# TwoFoot_SchDoc.net
KiCad netlist of a schematic drawn in Altium Designer
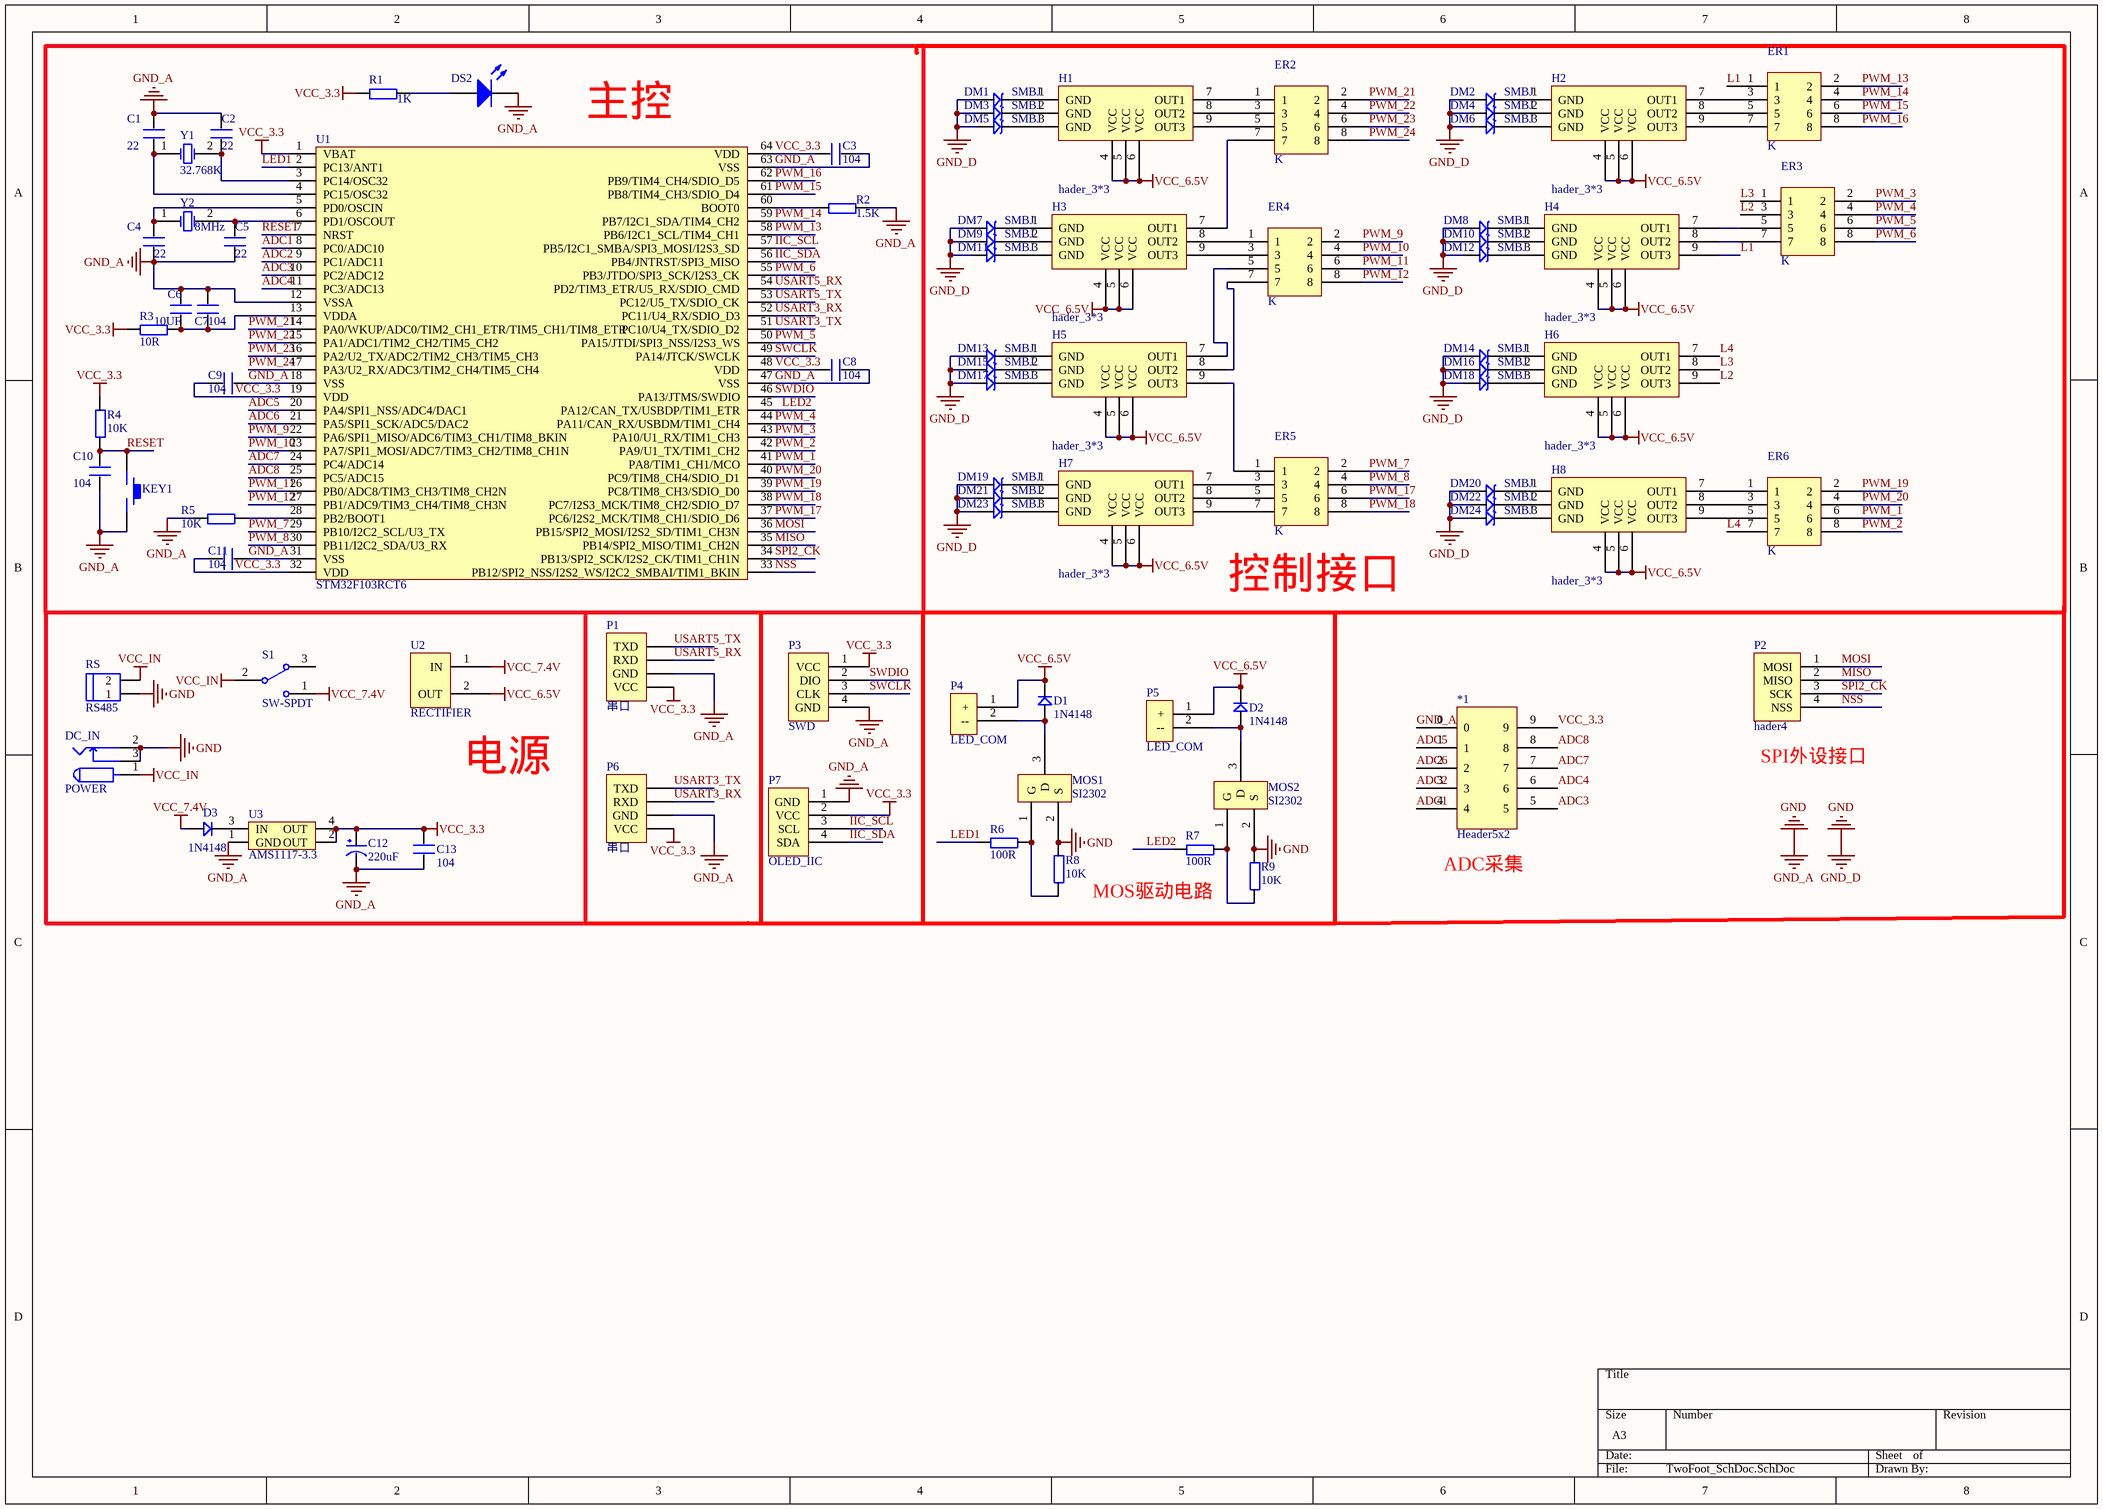
[diagram p0: TwoFoot_SchDoc.SchDoc]

(export (version "E")
  (design (tool "Eeschema 10.0.6"))
  (components
    (comp (ref "*1") (value "Header5x2") (footprint "HDR2X5") (libsource (lib "Schlib1") (part "Header5x2")))
    (comp (ref "C1") (value "22") (footprint "0603P") (libsource (lib "Schlib1") (part "C")))
    (comp (ref "C2") (value "22") (footprint "0603P") (libsource (lib "Schlib1") (part "C")))
    (comp (ref "C3") (value "104") (footprint "0603P") (libsource (lib "Schlib1") (part "C")))
    (comp (ref "C4") (value "22") (footprint "0603P") (libsource (lib "Schlib1") (part "C")))
    (comp (ref "C5") (value "22") (footprint "0603P") (libsource (lib "Schlib1") (part "C")))
    (comp (ref "C6") (value "10UF") (footprint "0603P") (libsource (lib "Schlib1") (part "C")))
    (comp (ref "C7") (value "104") (footprint "0603P") (libsource (lib "Schlib1") (part "C")))
    (comp (ref "C8") (value "104") (footprint "0603P") (libsource (lib "Schlib1") (part "C")))
    (comp (ref "C9") (value "104") (footprint "0603P") (libsource (lib "Schlib1") (part "C")))
    (comp (ref "C10") (value "104") (footprint "0603P") (libsource (lib "Schlib1") (part "C")))
    (comp (ref "C11") (value "104") (footprint "0603P") (libsource (lib "Schlib1") (part "C")))
    (comp (ref "C12") (value "220uF") (footprint "Cap1000uF") (libsource (lib "Schlib1") (part "CAP")))
    (comp (ref "C13") (value "104") (footprint "0603P") (libsource (lib "Schlib1") (part "C")))
    (comp (ref "D1") (value "1N4148") (footprint "DIODE_SOP") (libsource (lib "Schlib1") (part "D")))
    (comp (ref "D2") (value "1N4148") (footprint "DIODE_SOP") (libsource (lib "Schlib1") (part "D")))
    (comp (ref "D3") (value "1N4148") (footprint "DIODE_SOP") (libsource (lib "Schlib1") (part "D")))
    (comp (ref "DC_IN")
      (value "POWER")
      (footprint "POWER_INDC")
      (libsource (lib "Schlib1") (part "POWER_INDC"))
    )
    (comp (ref "DM1")
      (value "SMBJ")
      (footprint "SMBJ")
      (description "保险管5.0A")
      (libsource (lib "Schlib1") (part "SMBJ"))
    )
    (comp (ref "DM2")
      (value "SMBJ")
      (footprint "SMBJ")
      (description "保险管5.0A")
      (libsource (lib "Schlib1") (part "SMBJ"))
    )
    (comp (ref "DM3")
      (value "SMBJ")
      (footprint "SMBJ")
      (description "保险管5.0A")
      (libsource (lib "Schlib1") (part "SMBJ"))
    )
    (comp (ref "DM4")
      (value "SMBJ")
      (footprint "SMBJ")
      (description "保险管5.0A")
      (libsource (lib "Schlib1") (part "SMBJ"))
    )
    (comp (ref "DM5")
      (value "SMBJ")
      (footprint "SMBJ")
      (description "保险管5.0A")
      (libsource (lib "Schlib1") (part "SMBJ"))
    )
    (comp (ref "DM6")
      (value "SMBJ")
      (footprint "SMBJ")
      (description "保险管5.0A")
      (libsource (lib "Schlib1") (part "SMBJ"))
    )
    (comp (ref "DM7")
      (value "SMBJ")
      (footprint "SMBJ")
      (description "保险管5.0A")
      (libsource (lib "Schlib1") (part "SMBJ"))
    )
    (comp (ref "DM8")
      (value "SMBJ")
      (footprint "SMBJ")
      (description "保险管5.0A")
      (libsource (lib "Schlib1") (part "SMBJ"))
    )
    (comp (ref "DM9")
      (value "SMBJ")
      (footprint "SMBJ")
      (description "保险管5.0A")
      (libsource (lib "Schlib1") (part "SMBJ"))
    )
    (comp (ref "DM10")
      (value "SMBJ")
      (footprint "SMBJ")
      (description "保险管5.0A")
      (libsource (lib "Schlib1") (part "SMBJ"))
    )
    (comp (ref "DM11")
      (value "SMBJ")
      (footprint "SMBJ")
      (description "保险管5.0A")
      (libsource (lib "Schlib1") (part "SMBJ"))
    )
    (comp (ref "DM12")
      (value "SMBJ")
      (footprint "SMBJ")
      (description "保险管5.0A")
      (libsource (lib "Schlib1") (part "SMBJ"))
    )
    (comp (ref "DM13")
      (value "SMBJ")
      (footprint "SMBJ")
      (description "保险管5.0A")
      (libsource (lib "Schlib1") (part "SMBJ"))
    )
    (comp (ref "DM14")
      (value "SMBJ")
      (footprint "SMBJ")
      (description "保险管5.0A")
      (libsource (lib "Schlib1") (part "SMBJ"))
    )
    (comp (ref "DM15")
      (value "SMBJ")
      (footprint "SMBJ")
      (description "保险管5.0A")
      (libsource (lib "Schlib1") (part "SMBJ"))
    )
    (comp (ref "DM16")
      (value "SMBJ")
      (footprint "SMBJ")
      (description "保险管5.0A")
      (libsource (lib "Schlib1") (part "SMBJ"))
    )
    (comp (ref "DM17")
      (value "SMBJ")
      (footprint "SMBJ")
      (description "保险管5.0A")
      (libsource (lib "Schlib1") (part "SMBJ"))
    )
    (comp (ref "DM18")
      (value "SMBJ")
      (footprint "SMBJ")
      (description "保险管5.0A")
      (libsource (lib "Schlib1") (part "SMBJ"))
    )
    (comp (ref "DM19")
      (value "SMBJ")
      (footprint "SMBJ")
      (description "保险管5.0A")
      (libsource (lib "Schlib1") (part "SMBJ"))
    )
    (comp (ref "DM20")
      (value "SMBJ")
      (footprint "SMBJ")
      (description "保险管5.0A")
      (libsource (lib "Schlib1") (part "SMBJ"))
    )
    (comp (ref "DM21")
      (value "SMBJ")
      (footprint "SMBJ")
      (description "保险管5.0A")
      (libsource (lib "Schlib1") (part "SMBJ"))
    )
    (comp (ref "DM22")
      (value "SMBJ")
      (footprint "SMBJ")
      (description "保险管5.0A")
      (libsource (lib "Schlib1") (part "SMBJ"))
    )
    (comp (ref "DM23")
      (value "SMBJ")
      (footprint "SMBJ")
      (description "保险管5.0A")
      (libsource (lib "Schlib1") (part "SMBJ"))
    )
    (comp (ref "DM24")
      (value "SMBJ")
      (footprint "SMBJ")
      (description "保险管5.0A")
      (libsource (lib "Schlib1") (part "SMBJ"))
    )
    (comp (ref "DS2")
      (value "LED2")
      (footprint "SMDLED")
      (description "Typical RED, GREEN, YELLOW, AMBER GaAs LED")
      (fields (field (name "PUBLISHER") "Altium Limited"))
      (libsource (lib "Schlib1") (part "LED2"))
    )
    (comp (ref "ER1")
      (value "K")
      (footprint "8P4R_0603")
      (description "排阻")
      (libsource (lib "Schlib1") (part "0606_exclusion"))
    )
    (comp (ref "ER2")
      (value "K")
      (footprint "8P4R_0603")
      (description "排阻")
      (libsource (lib "Schlib1") (part "0606_exclusion"))
    )
    (comp (ref "ER3")
      (value "K")
      (footprint "8P4R_0603")
      (description "排阻")
      (libsource (lib "Schlib1") (part "0606_exclusion"))
    )
    (comp (ref "ER4")
      (value "K")
      (footprint "8P4R_0603")
      (description "排阻")
      (libsource (lib "Schlib1") (part "0606_exclusion"))
    )
    (comp (ref "ER5")
      (value "K")
      (footprint "8P4R_0603")
      (description "排阻")
      (libsource (lib "Schlib1") (part "0606_exclusion"))
    )
    (comp (ref "ER6")
      (value "K")
      (footprint "8P4R_0603")
      (description "排阻")
      (libsource (lib "Schlib1") (part "0606_exclusion"))
    )
    (comp (ref "H1")
      (value "hader_3*3")
      (footprint "heard3X3")
      (libsource (lib "Schlib1") (part "hader_3*3"))
    )
    (comp (ref "H2")
      (value "hader_3*3")
      (footprint "heard3X3")
      (libsource (lib "Schlib1") (part "hader_3*3"))
    )
    (comp (ref "H3")
      (value "hader_3*3")
      (footprint "heard3X3")
      (libsource (lib "Schlib1") (part "hader_3*3"))
    )
    (comp (ref "H4")
      (value "hader_3*3")
      (footprint "heard3X3")
      (libsource (lib "Schlib1") (part "hader_3*3"))
    )
    (comp (ref "H5")
      (value "hader_3*3")
      (footprint "heard3X3")
      (libsource (lib "Schlib1") (part "hader_3*3"))
    )
    (comp (ref "H6")
      (value "hader_3*3")
      (footprint "heard3X3")
      (libsource (lib "Schlib1") (part "hader_3*3"))
    )
    (comp (ref "H7")
      (value "hader_3*3")
      (footprint "heard3X3")
      (libsource (lib "Schlib1") (part "hader_3*3"))
    )
    (comp (ref "H8")
      (value "hader_3*3")
      (footprint "heard3X3")
      (libsource (lib "Schlib1") (part "hader_3*3"))
    )
    (comp (ref "KEY1") (value "KEY_M") (footprint "SW_PB2_A1") (libsource (lib "Schlib1") (part "KEY_M")))
    (comp (ref "MOS1") (value "SI2302") (footprint "SOT-23R") (libsource (lib "Schlib1") (part "MOS管")))
    (comp (ref "MOS2") (value "SI2302") (footprint "SOT-23R") (libsource (lib "Schlib1") (part "MOS管")))
    (comp (ref "P1")
      (value "串口")
      (footprint "HDR1X4")
      (fields (field (name "PUBLISHER") "Altium Limited"))
      (libsource (lib "Schlib1") (part "Header 4_1"))
    )
    (comp (ref "P2")
      (value "hader4")
      (footprint "HDR1X4 _NSS")
      (description "NSS")
      (libsource (lib "Schlib1") (part "hader4"))
    )
    (comp (ref "P3")
      (value "SWD")
      (footprint "HDR1X4 _S")
      (fields (field (name "PUBLISHER") "Altium Limited"))
      (libsource (lib "Schlib1") (part "Header 4"))
    )
    (comp (ref "P4") (value "LED_COM") (footprint "HDR2") (libsource (lib "Schlib1") (part "COM_LED")))
    (comp (ref "P5") (value "LED_COM") (footprint "HDR2") (libsource (lib "Schlib1") (part "COM_LED")))
    (comp (ref "P6")
      (value "串口")
      (footprint "HDR1X4")
      (fields (field (name "PUBLISHER") "Altium Limited"))
      (libsource (lib "Schlib1") (part "Header 4_1"))
    )
    (comp (ref "P7")
      (value "OLED_IIC")
      (footprint "HDR1X4 _OLED")
      (libsource (lib "Schlib1") (part "OLED_IIC"))
    )
    (comp (ref "R1") (value "1K") (footprint "0603P") (libsource (lib "Schlib1") (part "R")))
    (comp (ref "R2") (value "1.5K") (footprint "0603P") (libsource (lib "Schlib1") (part "R")))
    (comp (ref "R3") (value "10R") (footprint "0603P") (libsource (lib "Schlib1") (part "R")))
    (comp (ref "R4") (value "10K") (footprint "0603P") (libsource (lib "Schlib1") (part "R")))
    (comp (ref "R5") (value "10K") (footprint "0603P") (libsource (lib "Schlib1") (part "R")))
    (comp (ref "R6") (value "100R") (footprint "0603P") (libsource (lib "Schlib1") (part "R")))
    (comp (ref "R7") (value "100R") (footprint "0603P") (libsource (lib "Schlib1") (part "R")))
    (comp (ref "R8") (value "10K") (footprint "0603P") (libsource (lib "Schlib1") (part "R")))
    (comp (ref "R9") (value "10K") (footprint "0603P") (libsource (lib "Schlib1") (part "R")))
    (comp (ref "RS")
      (value "RS485")
      (footprint "POWER_INCOM")
      (libsource (lib "Schlib1") (part "POWER_INCOM"))
    )
    (comp (ref "S1")
      (value "SW-SPDT")
      (footprint "纽子开关")
      (description "开关")
      (fields (field (name "PUBLISHER") "Altium Limited"))
      (libsource (lib "Schlib1") (part "SW-SPDT"))
    )
    (comp (ref "U1")
      (value "STM32F103RCT6")
      (footprint "LQFP64")
      (libsource (lib "TwoFoot_Schlib") (part "STM32F103RCT6"))
    )
    (comp (ref "U2")
      (value "RECTIFIER")
      (footprint "RECTIFIER")
      (description "整流桥")
      (libsource (lib "Schlib1") (part "RECTIFIER"))
    )
    (comp (ref "U3") (value "AMS1117-3.3") (footprint "AMS1117") (libsource (lib "Schlib1") (part "AMS1117")))
    (comp (ref "Y1")
      (value "32.768K")
      (footprint "XTAL32")
      (description "Crystal Oscillator")
      (fields (field (name "PUBLISHER") "Altium Limited"))
      (libsource (lib "Schlib1") (part "XTAL"))
    )
    (comp (ref "Y2")
      (value "8MHz")
      (footprint "XTAL_US")
      (description "Crystal Oscillator")
      (fields (field (name "PUBLISHER") "Altium Limited"))
      (libsource (lib "Schlib1") (part "XTAL"))
    )
  )
  (nets
    (net (code "1") (name "/ADC1") (class "Default")
      (node (ref "*1") (pin "4") (pinfunction "4_4") (pintype "passive"))
      (node (ref "U1") (pin "8") (pinfunction "PC0/ADC10_8") (pintype "passive"))
    )
    (net (code "2") (name "/ADC2") (class "Default")
      (node (ref "*1") (pin "3") (pinfunction "3_3") (pintype "passive"))
      (node (ref "U1") (pin "9") (pinfunction "PC1/ADC11_9") (pintype "passive"))
    )
    (net (code "3") (name "/ADC3") (class "Default")
      (node (ref "*1") (pin "5") (pinfunction "5_5") (pintype "passive"))
      (node (ref "U1") (pin "10") (pinfunction "PC2/ADC12_10") (pintype "passive"))
    )
    (net (code "4") (name "/ADC4") (class "Default")
      (node (ref "*1") (pin "6") (pinfunction "6_6") (pintype "passive"))
      (node (ref "U1") (pin "11") (pinfunction "PC3/ADC13_11") (pintype "passive"))
    )
    (net (code "5") (name "/ADC5") (class "Default")
      (node (ref "*1") (pin "1") (pinfunction "1_1") (pintype "passive"))
      (node (ref "U1") (pin "20") (pinfunction "PA4/SPI1_NSS/ADC4/DAC1_20") (pintype "passive"))
    )
    (net (code "6") (name "/ADC6") (class "Default")
      (node (ref "*1") (pin "2") (pinfunction "2_2") (pintype "passive"))
      (node (ref "U1") (pin "21") (pinfunction "PA5/SPI1_SCK/ADC5/DAC2_21") (pintype "passive"))
    )
    (net (code "7") (name "/ADC7") (class "Default")
      (node (ref "*1") (pin "7") (pinfunction "7_7") (pintype "passive"))
      (node (ref "U1") (pin "24") (pinfunction "PC4/ADC14_24") (pintype "passive"))
    )
    (net (code "8") (name "/ADC8") (class "Default")
      (node (ref "*1") (pin "8") (pinfunction "8_8") (pintype "passive"))
      (node (ref "U1") (pin "25") (pinfunction "PC5/ADC15_25") (pintype "passive"))
    )
    (net (code "9") (name "/IIC_SCL") (class "Default")
      (node (ref "P7") (pin "3") (pinfunction "SCL_3") (pintype "passive"))
      (node (ref "U1") (pin "57") (pinfunction "PB5/I2C1_SMBA/SPI3_MOSI/I2S3_SD_57") (pintype "passive"))
    )
    (net (code "10") (name "/IIC_SDA") (class "Default")
      (node (ref "P7") (pin "4") (pinfunction "SDA_4") (pintype "passive"))
      (node (ref "U1") (pin "56") (pinfunction "PB4/JNTRST/SPI3_MISO_56") (pintype "passive"))
    )
    (net (code "11") (name "/L1") (class "Default")
      (node (ref "ER1") (pin "1") (pinfunction "1_1") (pintype "passive"))
      (node (ref "H4") (pin "9") (pinfunction "OUT3_9") (pintype "passive"))
    )
    (net (code "12") (name "/L2") (class "Default")
      (node (ref "ER3") (pin "3") (pinfunction "3_3") (pintype "passive"))
      (node (ref "H6") (pin "9") (pinfunction "OUT3_9") (pintype "passive"))
    )
    (net (code "13") (name "/L3") (class "Default")
      (node (ref "ER3") (pin "1") (pinfunction "1_1") (pintype "passive"))
      (node (ref "H6") (pin "8") (pinfunction "OUT2_8") (pintype "passive"))
    )
    (net (code "14") (name "/L4") (class "Default")
      (node (ref "ER6") (pin "7") (pinfunction "7_7") (pintype "passive"))
      (node (ref "H6") (pin "7") (pinfunction "OUT1_7") (pintype "passive"))
    )
    (net (code "15") (name "/LED1") (class "Default")
      (node (ref "R6") (pin "1") (pintype "passive"))
      (node (ref "U1") (pin "2") (pinfunction "PC13/ANT1_2") (pintype "passive"))
    )
    (net (code "16") (name "/LED2") (class "Default")
      (node (ref "R7") (pin "1") (pintype "passive"))
      (node (ref "U1") (pin "45") (pinfunction "PA12/CAN_TX/USBDP/TIM1_ETR_45") (pintype "passive"))
    )
    (net (code "17") (name "/MISO") (class "Default")
      (node (ref "P2") (pin "2") (pinfunction "MISO_2") (pintype "passive"))
      (node (ref "U1") (pin "35") (pinfunction "PB14/SPI2_MISO/TIM1_CH2N_35") (pintype "passive"))
    )
    (net (code "18") (name "/MOSI") (class "Default")
      (node (ref "P2") (pin "1") (pinfunction "MOSI_1") (pintype "passive"))
      (node (ref "U1") (pin "36") (pinfunction "PB15/SPI2_MOSI/I2S2_SD/TIM1_CH3N_36") (pintype "passive"))
    )
    (net (code "19") (name "/NSS") (class "Default")
      (node (ref "P2") (pin "4") (pinfunction "NSS_4") (pintype "passive"))
      (node (ref "U1") (pin "33") (pinfunction "PB12/SPI2_NSS/I2S2_WS/I2C2_SMBAI/TIM1_BKIN_33") (pintype "passive"))
    )
    (net (code "20") (name "/PWM_1") (class "Default")
      (node (ref "ER6") (pin "6") (pinfunction "6_6") (pintype "passive"))
      (node (ref "U1") (pin "41") (pinfunction "PA8/TIM1_CH1/MCO_41") (pintype "passive"))
    )
    (net (code "21") (name "/PWM_2") (class "Default")
      (node (ref "ER6") (pin "8") (pinfunction "8_8") (pintype "passive"))
      (node (ref "U1") (pin "42") (pinfunction "PA9/U1_TX/TIM1_CH2_42") (pintype "passive"))
    )
    (net (code "22") (name "/PWM_3") (class "Default")
      (node (ref "ER3") (pin "2") (pinfunction "2_2") (pintype "passive"))
      (node (ref "U1") (pin "43") (pinfunction "PA10/U1_RX/TIM1_CH3_43") (pintype "passive"))
    )
    (net (code "23") (name "/PWM_4") (class "Default")
      (node (ref "ER3") (pin "4") (pinfunction "4_4") (pintype "passive"))
      (node (ref "U1") (pin "44") (pinfunction "PA11/CAN_RX/USBDM/TIM1_CH4_44") (pintype "passive"))
    )
    (net (code "24") (name "/PWM_5") (class "Default")
      (node (ref "ER3") (pin "6") (pinfunction "6_6") (pintype "passive"))
      (node (ref "U1") (pin "50") (pinfunction "PA15/JTDI/SPI3_NSS/I2S3_WS_50") (pintype "passive"))
    )
    (net (code "25") (name "/PWM_6") (class "Default")
      (node (ref "ER3") (pin "8") (pinfunction "8_8") (pintype "passive"))
      (node (ref "U1") (pin "55") (pinfunction "PB3/JTDO/SPI3_SCK/I2S3_CK_55") (pintype "passive"))
    )
    (net (code "26") (name "/PWM_7") (class "Default")
      (node (ref "ER5") (pin "2") (pinfunction "2_2") (pintype "passive"))
      (node (ref "U1") (pin "29") (pinfunction "PB10/I2C2_SCL/U3_TX_29") (pintype "passive"))
    )
    (net (code "27") (name "/PWM_8") (class "Default")
      (node (ref "ER5") (pin "4") (pinfunction "4_4") (pintype "passive"))
      (node (ref "U1") (pin "30") (pinfunction "PB11/I2C2_SDA/U3_RX_30") (pintype "passive"))
    )
    (net (code "28") (name "/PWM_9") (class "Default")
      (node (ref "ER4") (pin "2") (pinfunction "2_2") (pintype "passive"))
      (node (ref "U1") (pin "22") (pinfunction "PA6/SPI1_MISO/ADC6/TIM3_CH1/TIM8_BKIN_22") (pintype "passive"))
    )
    (net (code "29") (name "/PWM_10") (class "Default")
      (node (ref "ER4") (pin "4") (pinfunction "4_4") (pintype "passive"))
      (node (ref "U1") (pin "23") (pinfunction "PA7/SPI1_MOSI/ADC7/TIM3_CH2/TIM8_CH1N_23") (pintype "passive"))
    )
    (net (code "30") (name "/PWM_11") (class "Default")
      (node (ref "ER4") (pin "6") (pinfunction "6_6") (pintype "passive"))
      (node (ref "U1") (pin "26") (pinfunction "PB0/ADC8/TIM3_CH3/TIM8_CH2N_26") (pintype "passive"))
    )
    (net (code "31") (name "/PWM_12") (class "Default")
      (node (ref "ER4") (pin "8") (pinfunction "8_8") (pintype "passive"))
      (node (ref "U1") (pin "27") (pinfunction "PB1/ADC9/TIM3_CH4/TIM8_CH3N_27") (pintype "passive"))
    )
    (net (code "32") (name "/PWM_13") (class "Default")
      (node (ref "ER1") (pin "2") (pinfunction "2_2") (pintype "passive"))
      (node (ref "U1") (pin "58") (pinfunction "PB6/I2C1_SCL/TIM4_CH1_58") (pintype "passive"))
    )
    (net (code "33") (name "/PWM_14") (class "Default")
      (node (ref "ER1") (pin "4") (pinfunction "4_4") (pintype "passive"))
      (node (ref "U1") (pin "59") (pinfunction "PB7/I2C1_SDA/TIM4_CH2_59") (pintype "passive"))
    )
    (net (code "34") (name "/PWM_15") (class "Default")
      (node (ref "ER1") (pin "6") (pinfunction "6_6") (pintype "passive"))
      (node (ref "U1") (pin "61") (pinfunction "PB8/TIM4_CH3/SDIO_D4_61") (pintype "passive"))
    )
    (net (code "35") (name "/PWM_16") (class "Default")
      (node (ref "ER1") (pin "8") (pinfunction "8_8") (pintype "passive"))
      (node (ref "U1") (pin "62") (pinfunction "PB9/TIM4_CH4/SDIO_D5_62") (pintype "passive"))
    )
    (net (code "36") (name "/PWM_17") (class "Default")
      (node (ref "ER5") (pin "6") (pinfunction "6_6") (pintype "passive"))
      (node (ref "U1") (pin "37") (pinfunction "PC6/I2S2_MCK/TIM8_CH1/SDIO_D6_37") (pintype "passive"))
    )
    (net (code "37") (name "/PWM_18") (class "Default")
      (node (ref "ER5") (pin "8") (pinfunction "8_8") (pintype "passive"))
      (node (ref "U1") (pin "38") (pinfunction "PC7/I2S3_MCK/TIM8_CH2/SDIO_D7_38") (pintype "passive"))
    )
    (net (code "38") (name "/PWM_19") (class "Default")
      (node (ref "ER6") (pin "2") (pinfunction "2_2") (pintype "passive"))
      (node (ref "U1") (pin "39") (pinfunction "PC8/TIM8_CH3/SDIO_D0_39") (pintype "passive"))
    )
    (net (code "39") (name "/PWM_20") (class "Default")
      (node (ref "ER6") (pin "4") (pinfunction "4_4") (pintype "passive"))
      (node (ref "U1") (pin "40") (pinfunction "PC9/TIM8_CH4/SDIO_D1_40") (pintype "passive"))
    )
    (net (code "40") (name "/PWM_21") (class "Default")
      (node (ref "ER2") (pin "2") (pinfunction "2_2") (pintype "passive"))
      (node (ref "U1") (pin "14") (pinfunction "PA0/WKUP/ADC0/TIM2_CH1_ETR/TIM5_CH1/TIM8_ETR_14") (pintype "passive"))
    )
    (net (code "41") (name "/PWM_22") (class "Default")
      (node (ref "ER2") (pin "4") (pinfunction "4_4") (pintype "passive"))
      (node (ref "U1") (pin "15") (pinfunction "PA1/ADC1/TIM2_CH2/TIM5_CH2_15") (pintype "passive"))
    )
    (net (code "42") (name "/PWM_23") (class "Default")
      (node (ref "ER2") (pin "6") (pinfunction "6_6") (pintype "passive"))
      (node (ref "U1") (pin "16") (pinfunction "PA2/U2_TX/ADC2/TIM2_CH3/TIM5_CH3_16") (pintype "passive"))
    )
    (net (code "43") (name "/PWM_24") (class "Default")
      (node (ref "ER2") (pin "8") (pinfunction "8_8") (pintype "passive"))
      (node (ref "U1") (pin "17") (pinfunction "PA3/U2_RX/ADC3/TIM2_CH4/TIM5_CH4_17") (pintype "passive"))
    )
    (net (code "44") (name "/RESET") (class "Default")
      (node (ref "C10") (pin "2") (pintype "passive"))
      (node (ref "KEY1") (pin "1") (pinfunction "1_1") (pintype "passive"))
      (node (ref "R4") (pin "1") (pintype "passive"))
      (node (ref "U1") (pin "7") (pinfunction "NRST_7") (pintype "passive"))
    )
    (net (code "45") (name "/SPI2_CK") (class "Default")
      (node (ref "P2") (pin "3") (pinfunction "SCK_3") (pintype "passive"))
      (node (ref "U1") (pin "34") (pinfunction "PB13/SPI2_SCK/I2S2_CK/TIM1_CH1N_34") (pintype "passive"))
    )
    (net (code "46") (name "/SWCLK") (class "Default")
      (node (ref "P3") (pin "3") (pinfunction "CLK_3") (pintype "passive"))
      (node (ref "U1") (pin "49") (pinfunction "PA14/JTCK/SWCLK_49") (pintype "passive"))
    )
    (net (code "47") (name "/SWDIO") (class "Default")
      (node (ref "P3") (pin "2") (pinfunction "DIO_2") (pintype "passive"))
      (node (ref "U1") (pin "46") (pinfunction "PA13/JTMS/SWDIO_46") (pintype "passive"))
    )
    (net (code "48") (name "/USART3_RX") (class "Default")
      (node (ref "P6") (pin "3") (pinfunction "RXD_3") (pintype "passive"))
      (node (ref "U1") (pin "52") (pinfunction "PC11/U4_RX/SDIO_D3_52") (pintype "passive"))
    )
    (net (code "49") (name "/USART3_TX") (class "Default")
      (node (ref "P6") (pin "4") (pinfunction "TXD_4") (pintype "passive"))
      (node (ref "U1") (pin "51") (pinfunction "PC10/U4_TX/SDIO_D2_51") (pintype "passive"))
    )
    (net (code "50") (name "/USART5_RX") (class "Default")
      (node (ref "P1") (pin "3") (pinfunction "RXD_3") (pintype "passive"))
      (node (ref "U1") (pin "54") (pinfunction "PD2/TIM3_ETR/U5_RX/SDIO_CMD_54") (pintype "passive"))
    )
    (net (code "51") (name "/USART5_TX") (class "Default")
      (node (ref "P1") (pin "4") (pinfunction "TXD_4") (pintype "passive"))
      (node (ref "U1") (pin "53") (pinfunction "PC12/U5_TX/SDIO_CK_53") (pintype "passive"))
    )
    (net (code "52") (name "GND") (class "Default")
      (node (ref "*1") (pin "0") (pinfunction "0_0") (pintype "passive"))
      (node (ref "C1") (pin "1") (pintype "passive"))
      (node (ref "C10") (pin "1") (pintype "passive"))
      (node (ref "C11") (pin "2") (pintype "passive"))
      (node (ref "C12") (pin "2") (pinfunction "GND_2") (pintype "passive"))
      (node (ref "C13") (pin "1") (pintype "passive"))
      (node (ref "C2") (pin "2") (pintype "passive"))
      (node (ref "C3") (pin "1") (pintype "passive"))
      (node (ref "C4") (pin "2") (pintype "passive"))
      (node (ref "C5") (pin "1") (pintype "passive"))
      (node (ref "C6") (pin "1") (pintype "passive"))
      (node (ref "C7") (pin "2") (pintype "passive"))
      (node (ref "C8") (pin "1") (pintype "passive"))
      (node (ref "C9") (pin "2") (pintype "passive"))
      (node (ref "DC_IN") (pin "2") (pintype "passive"))
      (node (ref "DC_IN") (pin "3") (pintype "passive"))
      (node (ref "DM1") (pin "1") (pintype "passive"))
      (node (ref "DM10") (pin "1") (pintype "passive"))
      (node (ref "DM11") (pin "1") (pintype "passive"))
      (node (ref "DM12") (pin "1") (pintype "passive"))
      (node (ref "DM13") (pin "1") (pintype "passive"))
      (node (ref "DM14") (pin "1") (pintype "passive"))
      (node (ref "DM15") (pin "1") (pintype "passive"))
      (node (ref "DM16") (pin "1") (pintype "passive"))
      (node (ref "DM17") (pin "1") (pintype "passive"))
      (node (ref "DM18") (pin "1") (pintype "passive"))
      (node (ref "DM19") (pin "1") (pintype "passive"))
      (node (ref "DM2") (pin "1") (pintype "passive"))
      (node (ref "DM20") (pin "1") (pintype "passive"))
      (node (ref "DM21") (pin "1") (pintype "passive"))
      (node (ref "DM22") (pin "1") (pintype "passive"))
      (node (ref "DM23") (pin "1") (pintype "passive"))
      (node (ref "DM24") (pin "1") (pintype "passive"))
      (node (ref "DM3") (pin "1") (pintype "passive"))
      (node (ref "DM4") (pin "1") (pintype "passive"))
      (node (ref "DM5") (pin "1") (pintype "passive"))
      (node (ref "DM6") (pin "1") (pintype "passive"))
      (node (ref "DM7") (pin "1") (pintype "passive"))
      (node (ref "DM8") (pin "1") (pintype "passive"))
      (node (ref "DM9") (pin "1") (pintype "passive"))
      (node (ref "DS2") (pin "2") (pinfunction "K_2") (pintype "passive"))
      (node (ref "KEY1") (pin "2") (pinfunction "2_2") (pintype "passive"))
      (node (ref "MOS1") (pin "2") (pinfunction "S_2") (pintype "passive"))
      (node (ref "MOS2") (pin "2") (pinfunction "S_2") (pintype "passive"))
      (node (ref "P1") (pin "2") (pinfunction "GND_2") (pintype "passive"))
      (node (ref "P3") (pin "4") (pinfunction "GND_4") (pintype "passive"))
      (node (ref "P6") (pin "2") (pinfunction "GND_2") (pintype "passive"))
      (node (ref "P7") (pin "1") (pinfunction "GND_1") (pintype "passive"))
      (node (ref "R2") (pin "2") (pintype "passive"))
      (node (ref "R5") (pin "1") (pintype "passive"))
      (node (ref "R8") (pin "2") (pintype "passive"))
      (node (ref "R9") (pin "2") (pintype "passive"))
      (node (ref "RS") (pin "1") (pinfunction "1_1") (pintype "passive"))
      (node (ref "U1") (pin "12") (pinfunction "VSSA_12") (pintype "passive"))
      (node (ref "U1") (pin "18") (pinfunction "VSS_18") (pintype "passive"))
      (node (ref "U1") (pin "31") (pinfunction "VSS_31") (pintype "passive"))
      (node (ref "U1") (pin "47") (pinfunction "VSS_47") (pintype "passive"))
      (node (ref "U1") (pin "63") (pinfunction "VSS_63") (pintype "passive"))
      (node (ref "U3") (pin "1") (pinfunction "GND_1") (pintype "passive"))
    )
    (net (code "53") (name "Net-(DM1-Pad2)") (class "Default")
      (node (ref "DM1") (pin "2") (pintype "passive"))
      (node (ref "H1") (pin "1") (pinfunction "GND_1") (pintype "passive"))
    )
    (net (code "54") (name "Net-(DM2-Pad2)") (class "Default")
      (node (ref "DM2") (pin "2") (pintype "passive"))
      (node (ref "H2") (pin "1") (pinfunction "GND_1") (pintype "passive"))
    )
    (net (code "55") (name "Net-(DM3-Pad2)") (class "Default")
      (node (ref "DM3") (pin "2") (pintype "passive"))
      (node (ref "H1") (pin "2") (pinfunction "GND_2") (pintype "passive"))
    )
    (net (code "56") (name "Net-(DM4-Pad2)") (class "Default")
      (node (ref "DM4") (pin "2") (pintype "passive"))
      (node (ref "H2") (pin "2") (pinfunction "GND_2") (pintype "passive"))
    )
    (net (code "57") (name "Net-(DM5-Pad2)") (class "Default")
      (node (ref "DM5") (pin "2") (pintype "passive"))
      (node (ref "H1") (pin "3") (pinfunction "GND_3") (pintype "passive"))
    )
    (net (code "58") (name "Net-(DM6-Pad2)") (class "Default")
      (node (ref "DM6") (pin "2") (pintype "passive"))
      (node (ref "H2") (pin "3") (pinfunction "GND_3") (pintype "passive"))
    )
    (net (code "59") (name "Net-(DM7-Pad2)") (class "Default")
      (node (ref "DM7") (pin "2") (pintype "passive"))
      (node (ref "H3") (pin "1") (pinfunction "GND_1") (pintype "passive"))
    )
    (net (code "60") (name "Net-(DM8-Pad2)") (class "Default")
      (node (ref "DM8") (pin "2") (pintype "passive"))
      (node (ref "H4") (pin "1") (pinfunction "GND_1") (pintype "passive"))
    )
    (net (code "61") (name "Net-(DM9-Pad2)") (class "Default")
      (node (ref "DM9") (pin "2") (pintype "passive"))
      (node (ref "H3") (pin "2") (pinfunction "GND_2") (pintype "passive"))
    )
    (net (code "62") (name "Net-(DM10-Pad2)") (class "Default")
      (node (ref "DM10") (pin "2") (pintype "passive"))
      (node (ref "H4") (pin "2") (pinfunction "GND_2") (pintype "passive"))
    )
    (net (code "63") (name "Net-(DM11-Pad2)") (class "Default")
      (node (ref "DM11") (pin "2") (pintype "passive"))
      (node (ref "H3") (pin "3") (pinfunction "GND_3") (pintype "passive"))
    )
    (net (code "64") (name "Net-(DM12-Pad2)") (class "Default")
      (node (ref "DM12") (pin "2") (pintype "passive"))
      (node (ref "H4") (pin "3") (pinfunction "GND_3") (pintype "passive"))
    )
    (net (code "65") (name "Net-(DM13-Pad2)") (class "Default")
      (node (ref "DM13") (pin "2") (pintype "passive"))
      (node (ref "H5") (pin "1") (pinfunction "GND_1") (pintype "passive"))
    )
    (net (code "66") (name "Net-(DM14-Pad2)") (class "Default")
      (node (ref "DM14") (pin "2") (pintype "passive"))
      (node (ref "H6") (pin "1") (pinfunction "GND_1") (pintype "passive"))
    )
    (net (code "67") (name "Net-(DM15-Pad2)") (class "Default")
      (node (ref "DM15") (pin "2") (pintype "passive"))
      (node (ref "H5") (pin "2") (pinfunction "GND_2") (pintype "passive"))
    )
    (net (code "68") (name "Net-(DM16-Pad2)") (class "Default")
      (node (ref "DM16") (pin "2") (pintype "passive"))
      (node (ref "H6") (pin "2") (pinfunction "GND_2") (pintype "passive"))
    )
    (net (code "69") (name "Net-(DM17-Pad2)") (class "Default")
      (node (ref "DM17") (pin "2") (pintype "passive"))
      (node (ref "H5") (pin "3") (pinfunction "GND_3") (pintype "passive"))
    )
    (net (code "70") (name "Net-(DM18-Pad2)") (class "Default")
      (node (ref "DM18") (pin "2") (pintype "passive"))
      (node (ref "H6") (pin "3") (pinfunction "GND_3") (pintype "passive"))
    )
    (net (code "71") (name "Net-(DM19-Pad2)") (class "Default")
      (node (ref "DM19") (pin "2") (pintype "passive"))
      (node (ref "H7") (pin "1") (pinfunction "GND_1") (pintype "passive"))
    )
    (net (code "72") (name "Net-(DM20-Pad2)") (class "Default")
      (node (ref "DM20") (pin "2") (pintype "passive"))
      (node (ref "H8") (pin "1") (pinfunction "GND_1") (pintype "passive"))
    )
    (net (code "73") (name "Net-(DM21-Pad2)") (class "Default")
      (node (ref "DM21") (pin "2") (pintype "passive"))
      (node (ref "H7") (pin "2") (pinfunction "GND_2") (pintype "passive"))
    )
    (net (code "74") (name "Net-(DM22-Pad2)") (class "Default")
      (node (ref "DM22") (pin "2") (pintype "passive"))
      (node (ref "H8") (pin "2") (pinfunction "GND_2") (pintype "passive"))
    )
    (net (code "75") (name "Net-(DM23-Pad2)") (class "Default")
      (node (ref "DM23") (pin "2") (pintype "passive"))
      (node (ref "H7") (pin "3") (pinfunction "GND_3") (pintype "passive"))
    )
    (net (code "76") (name "Net-(DM24-Pad2)") (class "Default")
      (node (ref "DM24") (pin "2") (pintype "passive"))
      (node (ref "H8") (pin "3") (pinfunction "GND_3") (pintype "passive"))
    )
    (net (code "77") (name "Net-(DS2-A)") (class "Default")
      (node (ref "DS2") (pin "1") (pinfunction "A_1") (pintype "passive"))
      (node (ref "R1") (pin "2") (pintype "passive"))
    )
    (net (code "78") (name "Net-(H1-OUT1)") (class "Default")
      (node (ref "ER2") (pin "1") (pinfunction "1_1") (pintype "passive"))
      (node (ref "H1") (pin "7") (pinfunction "OUT1_7") (pintype "passive"))
    )
    (net (code "79") (name "Net-(H1-OUT2)") (class "Default")
      (node (ref "ER2") (pin "3") (pinfunction "3_3") (pintype "passive"))
      (node (ref "H1") (pin "8") (pinfunction "OUT2_8") (pintype "passive"))
    )
    (net (code "80") (name "Net-(H1-OUT3)") (class "Default")
      (node (ref "ER2") (pin "5") (pinfunction "5_5") (pintype "passive"))
      (node (ref "H1") (pin "9") (pinfunction "OUT3_9") (pintype "passive"))
    )
    (net (code "81") (name "Net-(H2-OUT1)") (class "Default")
      (node (ref "ER1") (pin "3") (pinfunction "3_3") (pintype "passive"))
      (node (ref "H2") (pin "7") (pinfunction "OUT1_7") (pintype "passive"))
    )
    (net (code "82") (name "Net-(H2-OUT2)") (class "Default")
      (node (ref "ER1") (pin "5") (pinfunction "5_5") (pintype "passive"))
      (node (ref "H2") (pin "8") (pinfunction "OUT2_8") (pintype "passive"))
    )
    (net (code "83") (name "Net-(H2-OUT3)") (class "Default")
      (node (ref "ER1") (pin "7") (pinfunction "7_7") (pintype "passive"))
      (node (ref "H2") (pin "9") (pinfunction "OUT3_9") (pintype "passive"))
    )
    (net (code "84") (name "Net-(H3-OUT1)") (class "Default")
      (node (ref "ER2") (pin "7") (pinfunction "7_7") (pintype "passive"))
      (node (ref "H3") (pin "7") (pinfunction "OUT1_7") (pintype "passive"))
    )
    (net (code "85") (name "Net-(H3-OUT2)") (class "Default")
      (node (ref "ER4") (pin "1") (pinfunction "1_1") (pintype "passive"))
      (node (ref "H3") (pin "8") (pinfunction "OUT2_8") (pintype "passive"))
    )
    (net (code "86") (name "Net-(H3-OUT3)") (class "Default")
      (node (ref "ER4") (pin "3") (pinfunction "3_3") (pintype "passive"))
      (node (ref "H3") (pin "9") (pinfunction "OUT3_9") (pintype "passive"))
    )
    (net (code "87") (name "Net-(H4-OUT1)") (class "Default")
      (node (ref "ER3") (pin "5") (pinfunction "5_5") (pintype "passive"))
      (node (ref "H4") (pin "7") (pinfunction "OUT1_7") (pintype "passive"))
    )
    (net (code "88") (name "Net-(H4-OUT2)") (class "Default")
      (node (ref "ER3") (pin "7") (pinfunction "7_7") (pintype "passive"))
      (node (ref "H4") (pin "8") (pinfunction "OUT2_8") (pintype "passive"))
    )
    (net (code "89") (name "Net-(H5-OUT1)") (class "Default")
      (node (ref "ER4") (pin "5") (pinfunction "5_5") (pintype "passive"))
      (node (ref "H5") (pin "7") (pinfunction "OUT1_7") (pintype "passive"))
    )
    (net (code "90") (name "Net-(H5-OUT2)") (class "Default")
      (node (ref "ER4") (pin "7") (pinfunction "7_7") (pintype "passive"))
      (node (ref "H5") (pin "8") (pinfunction "OUT2_8") (pintype "passive"))
    )
    (net (code "91") (name "Net-(H5-OUT3)") (class "Default")
      (node (ref "ER5") (pin "1") (pinfunction "1_1") (pintype "passive"))
      (node (ref "H5") (pin "9") (pinfunction "OUT3_9") (pintype "passive"))
    )
    (net (code "92") (name "Net-(H7-OUT1)") (class "Default")
      (node (ref "ER5") (pin "3") (pinfunction "3_3") (pintype "passive"))
      (node (ref "H7") (pin "7") (pinfunction "OUT1_7") (pintype "passive"))
    )
    (net (code "93") (name "Net-(H7-OUT2)") (class "Default")
      (node (ref "ER5") (pin "5") (pinfunction "5_5") (pintype "passive"))
      (node (ref "H7") (pin "8") (pinfunction "OUT2_8") (pintype "passive"))
    )
    (net (code "94") (name "Net-(H7-OUT3)") (class "Default")
      (node (ref "ER5") (pin "7") (pinfunction "7_7") (pintype "passive"))
      (node (ref "H7") (pin "9") (pinfunction "OUT3_9") (pintype "passive"))
    )
    (net (code "95") (name "Net-(H8-OUT1)") (class "Default")
      (node (ref "ER6") (pin "1") (pinfunction "1_1") (pintype "passive"))
      (node (ref "H8") (pin "7") (pinfunction "OUT1_7") (pintype "passive"))
    )
    (net (code "96") (name "Net-(H8-OUT2)") (class "Default")
      (node (ref "ER6") (pin "3") (pinfunction "3_3") (pintype "passive"))
      (node (ref "H8") (pin "8") (pinfunction "OUT2_8") (pintype "passive"))
    )
    (net (code "97") (name "Net-(H8-OUT3)") (class "Default")
      (node (ref "ER6") (pin "5") (pinfunction "5_5") (pintype "passive"))
      (node (ref "H8") (pin "9") (pinfunction "OUT3_9") (pintype "passive"))
    )
    (net (code "98") (name "Net-(MOS1-D)") (class "Default")
      (node (ref "D1") (pin "1") (pintype "passive"))
      (node (ref "MOS1") (pin "3") (pinfunction "D_3") (pintype "passive"))
      (node (ref "P4") (pin "2") (pinfunction "--_2") (pintype "passive"))
    )
    (net (code "99") (name "Net-(MOS1-G)") (class "Default")
      (node (ref "MOS1") (pin "1") (pinfunction "G_1") (pintype "passive"))
      (node (ref "R6") (pin "2") (pintype "passive"))
      (node (ref "R8") (pin "1") (pintype "passive"))
    )
    (net (code "100") (name "Net-(MOS2-D)") (class "Default")
      (node (ref "D2") (pin "1") (pintype "passive"))
      (node (ref "MOS2") (pin "3") (pinfunction "D_3") (pintype "passive"))
      (node (ref "P5") (pin "2") (pinfunction "--_2") (pintype "passive"))
    )
    (net (code "101") (name "Net-(MOS2-G)") (class "Default")
      (node (ref "MOS2") (pin "1") (pinfunction "G_1") (pintype "passive"))
      (node (ref "R7") (pin "2") (pintype "passive"))
      (node (ref "R9") (pin "1") (pintype "passive"))
    )
    (net (code "102") (name "Net-(U1-BOOT0)") (class "Default")
      (node (ref "R2") (pin "1") (pintype "passive"))
      (node (ref "U1") (pin "60") (pinfunction "BOOT0_60") (pintype "passive"))
    )
    (net (code "103") (name "Net-(U1-PB2{slash}BOOT1)") (class "Default")
      (node (ref "R5") (pin "2") (pintype "passive"))
      (node (ref "U1") (pin "28") (pinfunction "PB2/BOOT1_28") (pintype "passive"))
    )
    (net (code "104") (name "Net-(U1-PC14{slash}OSC32)") (class "Default")
      (node (ref "C2") (pin "1") (pintype "passive"))
      (node (ref "U1") (pin "3") (pinfunction "PC14/OSC32_3") (pintype "passive"))
      (node (ref "Y1") (pin "2") (pinfunction "OSC2_2") (pintype "passive"))
    )
    (net (code "105") (name "Net-(U1-PC15{slash}OSC32)") (class "Default")
      (node (ref "C1") (pin "2") (pintype "passive"))
      (node (ref "U1") (pin "4") (pinfunction "PC15/OSC32_4") (pintype "passive"))
      (node (ref "Y1") (pin "1") (pinfunction "OSC1_1") (pintype "passive"))
    )
    (net (code "106") (name "Net-(U1-PD0{slash}OSCIN)") (class "Default")
      (node (ref "C4") (pin "1") (pintype "passive"))
      (node (ref "U1") (pin "5") (pinfunction "PD0/OSCIN_5") (pintype "passive"))
      (node (ref "Y2") (pin "1") (pinfunction "OSC1_1") (pintype "passive"))
    )
    (net (code "107") (name "Net-(U1-PD1{slash}OSCOUT)") (class "Default")
      (node (ref "C5") (pin "2") (pintype "passive"))
      (node (ref "U1") (pin "6") (pinfunction "PD1/OSCOUT_6") (pintype "passive"))
      (node (ref "Y2") (pin "2") (pinfunction "OSC2_2") (pintype "passive"))
    )
    (net (code "108") (name "Net-(U1-VDDA)") (class "Default")
      (node (ref "C6") (pin "2") (pintype "passive"))
      (node (ref "C7") (pin "1") (pintype "passive"))
      (node (ref "R3") (pin "2") (pintype "passive"))
      (node (ref "U1") (pin "13") (pinfunction "VDDA_13") (pintype "passive"))
    )
    (net (code "109") (name "Net-(U3-IN)") (class "Default")
      (node (ref "D3") (pin "2") (pintype "passive"))
      (node (ref "U3") (pin "3") (pinfunction "IN_3") (pintype "passive"))
    )
    (net (code "110") (name "VCC_3.3") (class "Default")
      (node (ref "*1") (pin "9") (pinfunction "9_9") (pintype "passive"))
      (node (ref "C11") (pin "1") (pintype "passive"))
      (node (ref "C12") (pin "1") (pinfunction "VCC_1") (pintype "passive"))
      (node (ref "C13") (pin "2") (pintype "passive"))
      (node (ref "C3") (pin "2") (pintype "passive"))
      (node (ref "C8") (pin "2") (pintype "passive"))
      (node (ref "C9") (pin "1") (pintype "passive"))
      (node (ref "P1") (pin "1") (pinfunction "VCC_1") (pintype "passive"))
      (node (ref "P3") (pin "1") (pinfunction "VCC_1") (pintype "passive"))
      (node (ref "P6") (pin "1") (pinfunction "VCC_1") (pintype "passive"))
      (node (ref "P7") (pin "2") (pinfunction "VCC_2") (pintype "passive"))
      (node (ref "R1") (pin "1") (pintype "passive"))
      (node (ref "R3") (pin "1") (pintype "passive"))
      (node (ref "R4") (pin "2") (pintype "passive"))
      (node (ref "U1") (pin "1") (pinfunction "VBAT_1") (pintype "passive"))
      (node (ref "U1") (pin "19") (pinfunction "VDD_19") (pintype "passive"))
      (node (ref "U1") (pin "32") (pinfunction "VDD_32") (pintype "passive"))
      (node (ref "U1") (pin "48") (pinfunction "VDD_48") (pintype "passive"))
      (node (ref "U1") (pin "64") (pinfunction "VDD_64") (pintype "passive"))
      (node (ref "U3") (pin "2") (pinfunction "OUT_2") (pintype "passive"))
      (node (ref "U3") (pin "4") (pinfunction "OUT_4") (pintype "passive"))
    )
    (net (code "111") (name "VCC_6.5V") (class "Default")
      (node (ref "D1") (pin "2") (pintype "passive"))
      (node (ref "D2") (pin "2") (pintype "passive"))
      (node (ref "H1") (pin "4") (pinfunction "VCC_4") (pintype "passive"))
      (node (ref "H1") (pin "5") (pinfunction "VCC_5") (pintype "passive"))
      (node (ref "H1") (pin "6") (pinfunction "VCC_6") (pintype "passive"))
      (node (ref "H2") (pin "4") (pinfunction "VCC_4") (pintype "passive"))
      (node (ref "H2") (pin "5") (pinfunction "VCC_5") (pintype "passive"))
      (node (ref "H2") (pin "6") (pinfunction "VCC_6") (pintype "passive"))
      (node (ref "H3") (pin "4") (pinfunction "VCC_4") (pintype "passive"))
      (node (ref "H3") (pin "5") (pinfunction "VCC_5") (pintype "passive"))
      (node (ref "H3") (pin "6") (pinfunction "VCC_6") (pintype "passive"))
      (node (ref "H4") (pin "4") (pinfunction "VCC_4") (pintype "passive"))
      (node (ref "H4") (pin "5") (pinfunction "VCC_5") (pintype "passive"))
      (node (ref "H4") (pin "6") (pinfunction "VCC_6") (pintype "passive"))
      (node (ref "H5") (pin "4") (pinfunction "VCC_4") (pintype "passive"))
      (node (ref "H5") (pin "5") (pinfunction "VCC_5") (pintype "passive"))
      (node (ref "H5") (pin "6") (pinfunction "VCC_6") (pintype "passive"))
      (node (ref "H6") (pin "4") (pinfunction "VCC_4") (pintype "passive"))
      (node (ref "H6") (pin "5") (pinfunction "VCC_5") (pintype "passive"))
      (node (ref "H6") (pin "6") (pinfunction "VCC_6") (pintype "passive"))
      (node (ref "H7") (pin "4") (pinfunction "VCC_4") (pintype "passive"))
      (node (ref "H7") (pin "5") (pinfunction "VCC_5") (pintype "passive"))
      (node (ref "H7") (pin "6") (pinfunction "VCC_6") (pintype "passive"))
      (node (ref "H8") (pin "4") (pinfunction "VCC_4") (pintype "passive"))
      (node (ref "H8") (pin "5") (pinfunction "VCC_5") (pintype "passive"))
      (node (ref "H8") (pin "6") (pinfunction "VCC_6") (pintype "passive"))
      (node (ref "P4") (pin "1") (pinfunction "+_1") (pintype "passive"))
      (node (ref "P5") (pin "1") (pinfunction "+_1") (pintype "passive"))
      (node (ref "U2") (pin "2") (pinfunction "OUT_2") (pintype "passive"))
    )
    (net (code "112") (name "VCC_7.4V") (class "Default")
      (node (ref "D3") (pin "1") (pintype "passive"))
      (node (ref "S1") (pin "1") (pinfunction "1_1") (pintype "passive"))
      (node (ref "U2") (pin "1") (pinfunction "IN_1") (pintype "passive"))
    )
    (net (code "113") (name "VCC_IN") (class "Default")
      (node (ref "DC_IN") (pin "1") (pintype "passive"))
      (node (ref "RS") (pin "2") (pinfunction "2_2") (pintype "passive"))
      (node (ref "S1") (pin "2") (pinfunction "2_2") (pintype "passive"))
    )
    (net (code "114") (name "unconnected-(S1-Pad3)") (class "Default")
      (node (ref "S1") (pin "3") (pinfunction "3_3") (pintype "passive"))
    )
  )
)
